# Logic_SchematicV4-w-DRC.net
KiCad netlist of a schematic drawn in EAGLE
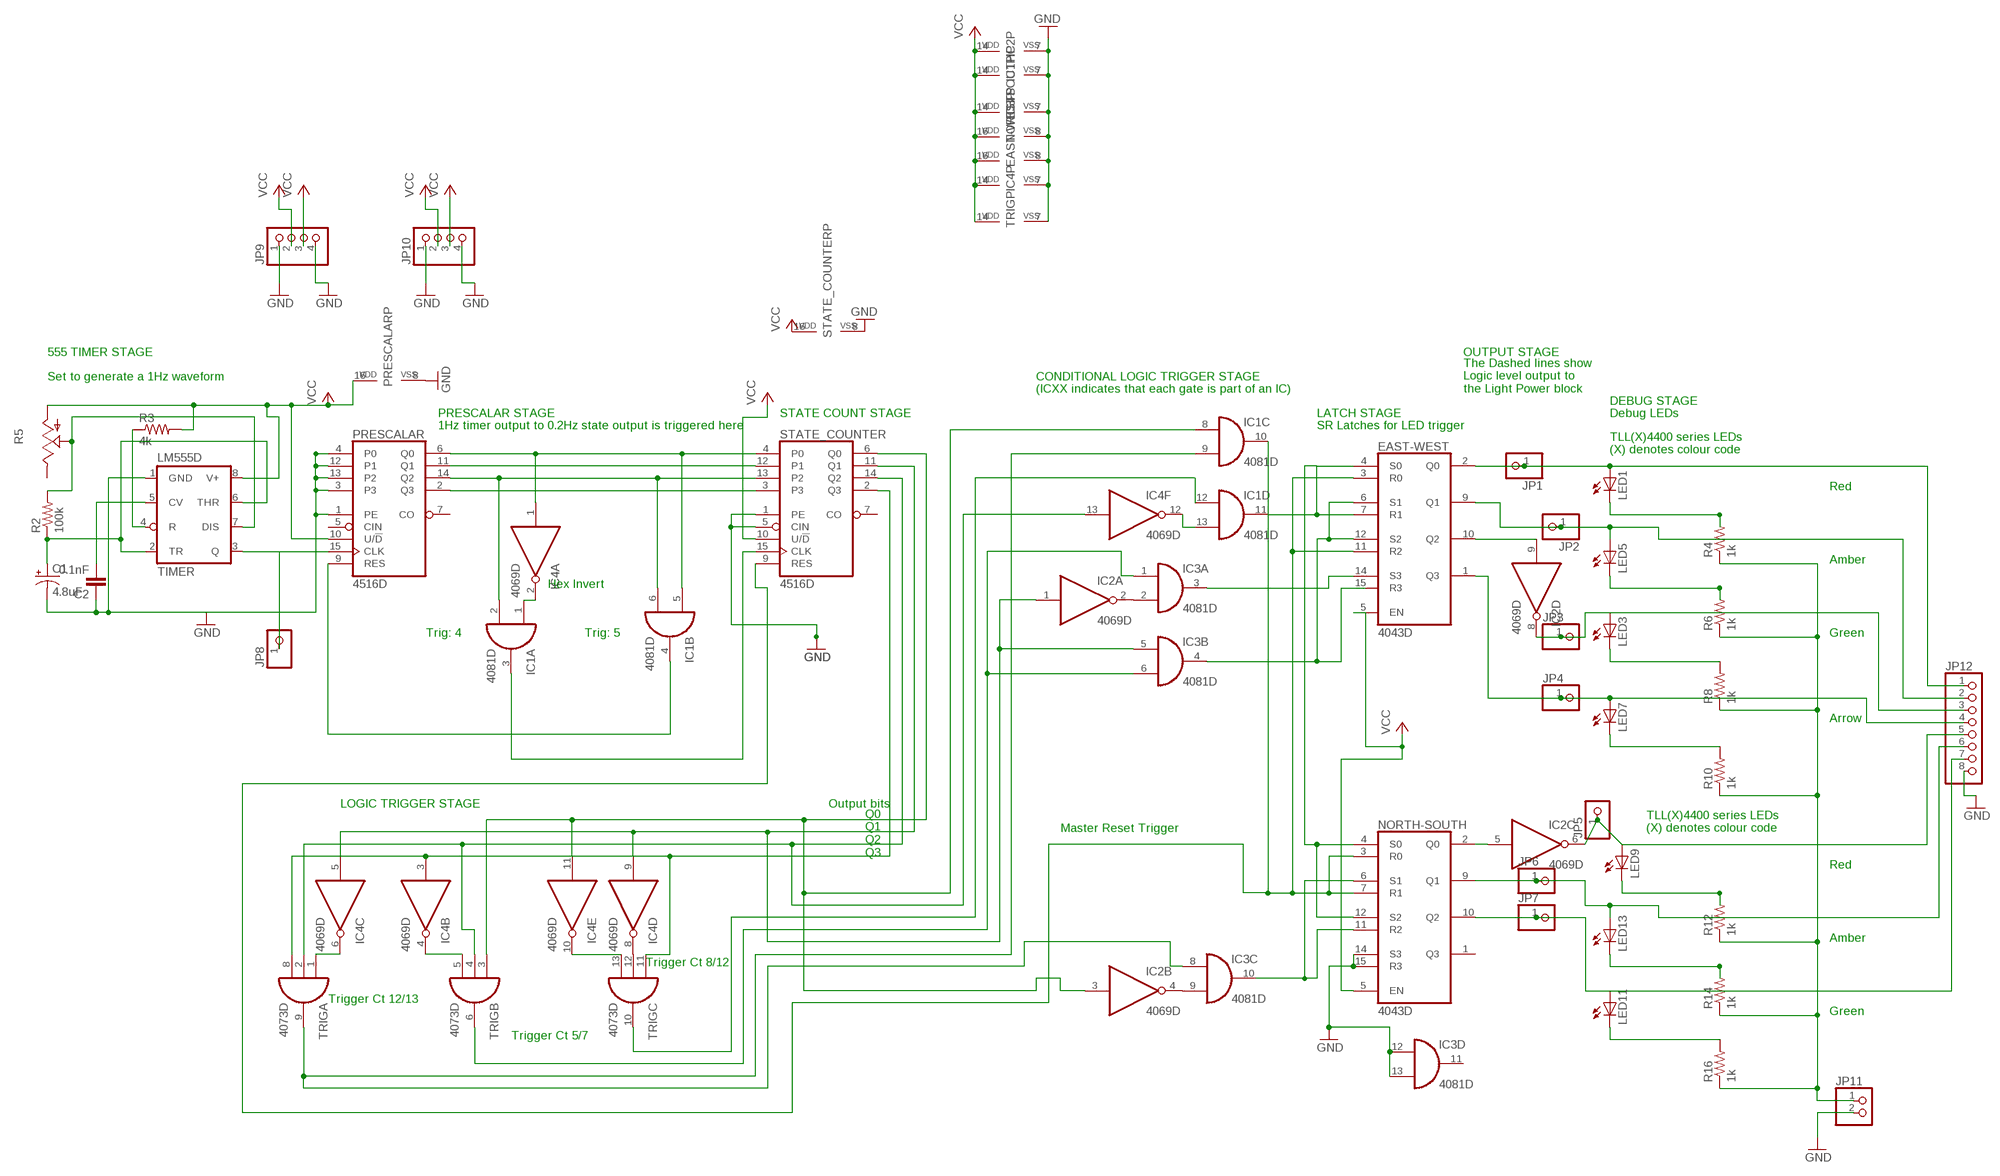
[diagram p0: schematic, sheet 1]

(export (version "E")
  (design (tool "Eeschema 10.0.6"))
  (components
    (comp (ref "C1")
      (value "4.8uF")
      (footprint "eagle-import:E5-8,5")
      (libsource (lib "eagle-import") (part "CPOL-USE5-8.5"))
    )
    (comp (ref "C2")
      (value "0.1nF")
      (footprint "eagle-import:C0805")
      (libsource (lib "eagle-import") (part "C-EUC0805"))
    )
    (comp (ref "EAST-WEST")
      (value "4043D")
      (footprint "eagle-import:SO16")
      (libsource (lib "eagle-import") (part "4043D"))
    )
    (comp (ref "IC1")
      (value "4081D")
      (footprint "eagle-import:SO14")
      (libsource (lib "eagle-import") (part "4081D"))
    )
    (comp (ref "IC2")
      (value "4069D")
      (footprint "eagle-import:SO14")
      (libsource (lib "eagle-import") (part "4069D"))
    )
    (comp (ref "IC3")
      (value "4081D")
      (footprint "eagle-import:SO14")
      (libsource (lib "eagle-import") (part "4081D"))
    )
    (comp (ref "IC4")
      (value "4069D")
      (footprint "eagle-import:SO14")
      (libsource (lib "eagle-import") (part "4069D"))
    )
    (comp (ref "JP1")
      (value "PINHD-1X1")
      (footprint "eagle-import:1X01")
      (libsource (lib "eagle-import") (part "PINHD-1X1"))
    )
    (comp (ref "JP2")
      (value "PINHD-1X1")
      (footprint "eagle-import:1X01")
      (libsource (lib "eagle-import") (part "PINHD-1X1"))
    )
    (comp (ref "JP3")
      (value "PINHD-1X1")
      (footprint "eagle-import:1X01")
      (libsource (lib "eagle-import") (part "PINHD-1X1"))
    )
    (comp (ref "JP4")
      (value "PINHD-1X1")
      (footprint "eagle-import:1X01")
      (libsource (lib "eagle-import") (part "PINHD-1X1"))
    )
    (comp (ref "JP5")
      (value "PINHD-1X1")
      (footprint "eagle-import:1X01")
      (libsource (lib "eagle-import") (part "PINHD-1X1"))
    )
    (comp (ref "JP6")
      (value "PINHD-1X1")
      (footprint "eagle-import:1X01")
      (libsource (lib "eagle-import") (part "PINHD-1X1"))
    )
    (comp (ref "JP7")
      (value "PINHD-1X1")
      (footprint "eagle-import:1X01")
      (libsource (lib "eagle-import") (part "PINHD-1X1"))
    )
    (comp (ref "JP8")
      (value "PINHD-1X1")
      (footprint "eagle-import:1X01")
      (libsource (lib "eagle-import") (part "PINHD-1X1"))
    )
    (comp (ref "JP9")
      (value "PINHD-1X4")
      (footprint "eagle-import:1X04")
      (libsource (lib "eagle-import") (part "PINHD-1X4"))
    )
    (comp (ref "JP10")
      (value "PINHD-1X4")
      (footprint "eagle-import:1X04")
      (libsource (lib "eagle-import") (part "PINHD-1X4"))
    )
    (comp (ref "JP11")
      (value "PINHD-1X2")
      (footprint "eagle-import:1X02")
      (libsource (lib "eagle-import") (part "PINHD-1X2"))
    )
    (comp (ref "JP12")
      (value "PINHD-1X8")
      (footprint "eagle-import:1X08")
      (libsource (lib "eagle-import") (part "PINHD-1X8"))
    )
    (comp (ref "LED1")
      (value "LEDCHIP-LED0805")
      (footprint "eagle-import:CHIP-LED0805")
      (libsource (lib "eagle-import") (part "LEDCHIP-LED0805"))
    )
    (comp (ref "LED3")
      (value "LEDCHIP-LED0805")
      (footprint "eagle-import:CHIP-LED0805")
      (libsource (lib "eagle-import") (part "LEDCHIP-LED0805"))
    )
    (comp (ref "LED5")
      (value "LEDCHIP-LED0805")
      (footprint "eagle-import:CHIP-LED0805")
      (libsource (lib "eagle-import") (part "LEDCHIP-LED0805"))
    )
    (comp (ref "LED7")
      (value "LEDCHIP-LED0805")
      (footprint "eagle-import:CHIP-LED0805")
      (libsource (lib "eagle-import") (part "LEDCHIP-LED0805"))
    )
    (comp (ref "LED9")
      (value "LEDCHIP-LED0805")
      (footprint "eagle-import:CHIP-LED0805")
      (libsource (lib "eagle-import") (part "LEDCHIP-LED0805"))
    )
    (comp (ref "LED11")
      (value "LEDCHIP-LED0805")
      (footprint "eagle-import:CHIP-LED0805")
      (libsource (lib "eagle-import") (part "LEDCHIP-LED0805"))
    )
    (comp (ref "LED13")
      (value "LEDCHIP-LED0805")
      (footprint "eagle-import:CHIP-LED0805")
      (libsource (lib "eagle-import") (part "LEDCHIP-LED0805"))
    )
    (comp (ref "NORTH-SOUTH")
      (value "4043D")
      (footprint "eagle-import:SO16")
      (libsource (lib "eagle-import") (part "4043D"))
    )
    (comp (ref "PRESCALAR")
      (value "4516D")
      (footprint "eagle-import:SO16")
      (libsource (lib "eagle-import") (part "4516D"))
    )
    (comp (ref "R2")
      (value "100k")
      (footprint "eagle-import:M0805")
      (libsource (lib "eagle-import") (part "R-US_M0805"))
    )
    (comp (ref "R3")
      (value "4k")
      (footprint "eagle-import:M0805")
      (libsource (lib "eagle-import") (part "R-US_M0805"))
    )
    (comp (ref "R4")
      (value "1k")
      (footprint "eagle-import:M0805")
      (libsource (lib "eagle-import") (part "R-US_M0805"))
    )
    (comp (ref "R5")
      (value "TRIM_US-B25P")
      (footprint "eagle-import:B25P")
      (libsource (lib "eagle-import") (part "TRIM_US-B25P"))
    )
    (comp (ref "R6")
      (value "1k")
      (footprint "eagle-import:M0805")
      (libsource (lib "eagle-import") (part "R-US_M0805"))
    )
    (comp (ref "R8")
      (value "1k")
      (footprint "eagle-import:M0805")
      (libsource (lib "eagle-import") (part "R-US_M0805"))
    )
    (comp (ref "R10")
      (value "1k")
      (footprint "eagle-import:M0805")
      (libsource (lib "eagle-import") (part "R-US_M0805"))
    )
    (comp (ref "R12")
      (value "1k")
      (footprint "eagle-import:M0805")
      (libsource (lib "eagle-import") (part "R-US_M0805"))
    )
    (comp (ref "R14")
      (value "1k")
      (footprint "eagle-import:M0805")
      (libsource (lib "eagle-import") (part "R-US_M0805"))
    )
    (comp (ref "R16")
      (value "1k")
      (footprint "eagle-import:M0805")
      (libsource (lib "eagle-import") (part "R-US_M0805"))
    )
    (comp (ref "STATE_COUNTER")
      (value "4516D")
      (footprint "eagle-import:SO16")
      (libsource (lib "eagle-import") (part "4516D"))
    )
    (comp (ref "TIMER")
      (value "LM555D")
      (footprint "eagle-import:SO08")
      (libsource (lib "eagle-import") (part "555DLM"))
    )
    (comp (ref "TRIG")
      (value "4073D")
      (footprint "eagle-import:SO14")
      (libsource (lib "eagle-import") (part "4073D"))
    )
  )
  (nets
    (net (code "1") (name "GND") (class "Default")
      (node (ref "C1") (pin "-") (pinfunction "-_-") (pintype "passive"))
      (node (ref "C2") (pin "1") (pinfunction "1_1") (pintype "passive"))
      (node (ref "EAST-WEST") (pin "8") (pinfunction "VSS_8") (pintype "power_in"))
      (node (ref "IC1") (pin "7") (pinfunction "VSS_7") (pintype "power_in"))
      (node (ref "IC2") (pin "7") (pinfunction "VSS_7") (pintype "power_in"))
      (node (ref "IC3") (pin "12") (pinfunction "I0_12") (pintype "input"))
      (node (ref "IC3") (pin "13") (pinfunction "I1_13") (pintype "input"))
      (node (ref "IC3") (pin "7") (pinfunction "VSS_7") (pintype "power_in"))
      (node (ref "IC4") (pin "7") (pinfunction "VSS_7") (pintype "power_in"))
      (node (ref "JP10") (pin "1") (pinfunction "1_1") (pintype "passive"))
      (node (ref "JP10") (pin "4") (pinfunction "4_4") (pintype "passive"))
      (node (ref "JP11") (pin "2") (pinfunction "2_2") (pintype "passive"))
      (node (ref "JP12") (pin "8") (pinfunction "8_8") (pintype "passive"))
      (node (ref "JP9") (pin "1") (pinfunction "1_1") (pintype "passive"))
      (node (ref "JP9") (pin "4") (pinfunction "4_4") (pintype "passive"))
      (node (ref "NORTH-SOUTH") (pin "14") (pinfunction "S3_14") (pintype "input"))
      (node (ref "NORTH-SOUTH") (pin "15") (pinfunction "R3_15") (pintype "input"))
      (node (ref "NORTH-SOUTH") (pin "8") (pinfunction "VSS_8") (pintype "power_in"))
      (node (ref "PRESCALAR") (pin "1") (pinfunction "PE_1") (pintype "input"))
      (node (ref "PRESCALAR") (pin "12") (pinfunction "P1_12") (pintype "input"))
      (node (ref "PRESCALAR") (pin "13") (pinfunction "P2_13") (pintype "input"))
      (node (ref "PRESCALAR") (pin "3") (pinfunction "P3_3") (pintype "input"))
      (node (ref "PRESCALAR") (pin "4") (pinfunction "P0_4") (pintype "input"))
      (node (ref "PRESCALAR") (pin "8") (pinfunction "VSS_8") (pintype "power_in"))
      (node (ref "STATE_COUNTER") (pin "1") (pinfunction "PE_1") (pintype "input"))
      (node (ref "STATE_COUNTER") (pin "5") (pinfunction "CIN_5") (pintype "input"))
      (node (ref "STATE_COUNTER") (pin "8") (pinfunction "VSS_8") (pintype "power_in"))
      (node (ref "TIMER") (pin "1") (pinfunction "GND_1") (pintype "power_in"))
      (node (ref "TRIG") (pin "7") (pinfunction "VSS_7") (pintype "power_in"))
    )
    (net (code "2") (name "Net-(EAST-WESTA-Q0)") (class "Default")
      (node (ref "EAST-WEST") (pin "2") (pinfunction "Q0_2") (pintype "output"))
      (node (ref "JP1") (pin "1") (pinfunction "1_1") (pintype "passive"))
      (node (ref "JP12") (pin "1") (pinfunction "1_1") (pintype "passive"))
      (node (ref "LED1") (pin "A") (pinfunction "A_A") (pintype "passive"))
    )
    (net (code "3") (name "Net-(EAST-WESTA-Q1)") (class "Default")
      (node (ref "EAST-WEST") (pin "9") (pinfunction "Q1_9") (pintype "output"))
      (node (ref "JP12") (pin "2") (pinfunction "2_2") (pintype "passive"))
      (node (ref "JP2") (pin "1") (pinfunction "1_1") (pintype "passive"))
      (node (ref "LED5") (pin "A") (pinfunction "A_A") (pintype "passive"))
    )
    (net (code "4") (name "Net-(EAST-WESTA-Q2)") (class "Default")
      (node (ref "EAST-WEST") (pin "10") (pinfunction "Q2_10") (pintype "output"))
      (node (ref "IC2") (pin "9") (pinfunction "I_9") (pintype "input"))
    )
    (net (code "5") (name "Net-(EAST-WESTA-Q3)") (class "Default")
      (node (ref "EAST-WEST") (pin "1") (pinfunction "Q3_1") (pintype "output"))
      (node (ref "JP12") (pin "4") (pinfunction "4_4") (pintype "passive"))
      (node (ref "JP4") (pin "1") (pinfunction "1_1") (pintype "passive"))
      (node (ref "LED7") (pin "A") (pinfunction "A_A") (pintype "passive"))
    )
    (net (code "6") (name "Net-(EAST-WESTA-R0)") (class "Default")
      (node (ref "EAST-WEST") (pin "11") (pinfunction "R2_11") (pintype "input"))
      (node (ref "EAST-WEST") (pin "3") (pinfunction "R0_3") (pintype "input"))
      (node (ref "IC1") (pin "10") (pinfunction "O_10") (pintype "output"))
      (node (ref "NORTH-SOUTH") (pin "3") (pinfunction "R0_3") (pintype "input"))
      (node (ref "NORTH-SOUTH") (pin "7") (pinfunction "R1_7") (pintype "input"))
      (node (ref "STATE_COUNTER") (pin "9") (pinfunction "RES_9") (pintype "input"))
    )
    (net (code "7") (name "Net-(EAST-WESTA-R1)") (class "Default")
      (node (ref "EAST-WEST") (pin "4") (pinfunction "S0_4") (pintype "input"))
      (node (ref "EAST-WEST") (pin "7") (pinfunction "R1_7") (pintype "input"))
      (node (ref "IC1") (pin "11") (pinfunction "O_11") (pintype "output"))
      (node (ref "NORTH-SOUTH") (pin "12") (pinfunction "S2_12") (pintype "input"))
      (node (ref "NORTH-SOUTH") (pin "4") (pinfunction "S0_4") (pintype "input"))
    )
    (net (code "8") (name "Net-(EAST-WESTA-S1)") (class "Default")
      (node (ref "EAST-WEST") (pin "12") (pinfunction "S2_12") (pintype "input"))
      (node (ref "EAST-WEST") (pin "6") (pinfunction "S1_6") (pintype "input"))
      (node (ref "IC3") (pin "4") (pinfunction "O_4") (pintype "output"))
    )
    (net (code "9") (name "Net-(EAST-WESTA-S3)") (class "Default")
      (node (ref "EAST-WEST") (pin "14") (pinfunction "S3_14") (pintype "input"))
      (node (ref "IC3") (pin "3") (pinfunction "O_3") (pintype "output"))
    )
    (net (code "10") (name "Net-(IC1A-I0)") (class "Default")
      (node (ref "IC1") (pin "1") (pinfunction "I0_1") (pintype "input"))
      (node (ref "IC4") (pin "2") (pinfunction "O_2") (pintype "output"))
    )
    (net (code "11") (name "Net-(IC1A-I1)") (class "Default")
      (node (ref "IC1") (pin "2") (pinfunction "I1_2") (pintype "input"))
      (node (ref "IC1") (pin "6") (pinfunction "I1_6") (pintype "input"))
      (node (ref "PRESCALAR") (pin "14") (pinfunction "Q2_14") (pintype "output"))
      (node (ref "STATE_COUNTER") (pin "13") (pinfunction "P2_13") (pintype "input"))
    )
    (net (code "12") (name "Net-(IC1A-O)") (class "Default")
      (node (ref "IC1") (pin "3") (pinfunction "O_3") (pintype "output"))
      (node (ref "STATE_COUNTER") (pin "15") (pinfunction "CLK_15") (pintype "input"))
    )
    (net (code "13") (name "Net-(IC1B-I0)") (class "Default")
      (node (ref "IC1") (pin "5") (pinfunction "I0_5") (pintype "input"))
      (node (ref "IC4") (pin "1") (pinfunction "I_1") (pintype "input"))
      (node (ref "PRESCALAR") (pin "6") (pinfunction "Q0_6") (pintype "output"))
      (node (ref "STATE_COUNTER") (pin "4") (pinfunction "P0_4") (pintype "input"))
    )
    (net (code "14") (name "Net-(IC1B-O)") (class "Default")
      (node (ref "IC1") (pin "4") (pinfunction "O_4") (pintype "output"))
      (node (ref "PRESCALAR") (pin "9") (pinfunction "RES_9") (pintype "input"))
    )
    (net (code "15") (name "Net-(IC1C-I0)") (class "Default")
      (node (ref "IC1") (pin "8") (pinfunction "I0_8") (pintype "input"))
      (node (ref "IC2") (pin "3") (pinfunction "I_3") (pintype "input"))
      (node (ref "IC4") (pin "11") (pinfunction "I_11") (pintype "input"))
      (node (ref "STATE_COUNTER") (pin "6") (pinfunction "Q0_6") (pintype "output"))
      (node (ref "TRIG") (pin "3") (pinfunction "I0_3") (pintype "input"))
    )
    (net (code "16") (name "Net-(IC1C-I1)") (class "Default")
      (node (ref "IC1") (pin "9") (pinfunction "I1_9") (pintype "input"))
      (node (ref "IC3") (pin "8") (pinfunction "I0_8") (pintype "input"))
      (node (ref "TRIG") (pin "9") (pinfunction "O_9") (pintype "output"))
    )
    (net (code "17") (name "Net-(IC1D-I0)") (class "Default")
      (node (ref "IC1") (pin "12") (pinfunction "I0_12") (pintype "input"))
      (node (ref "TRIG") (pin "10") (pinfunction "O_10") (pintype "output"))
    )
    (net (code "18") (name "Net-(IC1D-I1)") (class "Default")
      (node (ref "IC1") (pin "13") (pinfunction "I1_13") (pintype "input"))
      (node (ref "IC4") (pin "12") (pinfunction "O_12") (pintype "output"))
    )
    (net (code "19") (name "Net-(IC2A-I)") (class "Default")
      (node (ref "IC2") (pin "1") (pinfunction "I_1") (pintype "input"))
      (node (ref "IC3") (pin "5") (pinfunction "I0_5") (pintype "input"))
      (node (ref "IC4") (pin "5") (pinfunction "I_5") (pintype "input"))
      (node (ref "IC4") (pin "9") (pinfunction "I_9") (pintype "input"))
      (node (ref "STATE_COUNTER") (pin "11") (pinfunction "Q1_11") (pintype "output"))
    )
    (net (code "20") (name "Net-(IC2A-O)") (class "Default")
      (node (ref "IC2") (pin "2") (pinfunction "O_2") (pintype "output"))
      (node (ref "IC3") (pin "2") (pinfunction "I1_2") (pintype "input"))
    )
    (net (code "21") (name "Net-(IC2B-O)") (class "Default")
      (node (ref "IC2") (pin "4") (pinfunction "O_4") (pintype "output"))
      (node (ref "IC3") (pin "9") (pinfunction "I1_9") (pintype "input"))
    )
    (net (code "22") (name "Net-(IC2C-I)") (class "Default")
      (node (ref "IC2") (pin "5") (pinfunction "I_5") (pintype "input"))
      (node (ref "NORTH-SOUTH") (pin "2") (pinfunction "Q0_2") (pintype "output"))
    )
    (net (code "23") (name "Net-(IC2C-O)") (class "Default")
      (node (ref "IC2") (pin "6") (pinfunction "O_6") (pintype "output"))
      (node (ref "JP12") (pin "5") (pinfunction "5_5") (pintype "passive"))
      (node (ref "JP5") (pin "1") (pinfunction "1_1") (pintype "passive"))
      (node (ref "LED9") (pin "A") (pinfunction "A_A") (pintype "passive"))
    )
    (net (code "24") (name "Net-(IC2D-O)") (class "Default")
      (node (ref "IC2") (pin "8") (pinfunction "O_8") (pintype "output"))
      (node (ref "JP12") (pin "3") (pinfunction "3_3") (pintype "passive"))
      (node (ref "JP3") (pin "1") (pinfunction "1_1") (pintype "passive"))
      (node (ref "LED3") (pin "A") (pinfunction "A_A") (pintype "passive"))
    )
    (net (code "25") (name "Net-(IC3A-I0)") (class "Default")
      (node (ref "IC3") (pin "1") (pinfunction "I0_1") (pintype "input"))
      (node (ref "IC3") (pin "6") (pinfunction "I1_6") (pintype "input"))
      (node (ref "TRIG") (pin "6") (pinfunction "O_6") (pintype "output"))
    )
    (net (code "26") (name "Net-(IC3C-O)") (class "Default")
      (node (ref "IC3") (pin "10") (pinfunction "O_10") (pintype "output"))
      (node (ref "NORTH-SOUTH") (pin "11") (pinfunction "R2_11") (pintype "input"))
      (node (ref "NORTH-SOUTH") (pin "6") (pinfunction "S1_6") (pintype "input"))
    )
    (net (code "27") (name "Net-(IC4B-I)") (class "Default")
      (node (ref "IC4") (pin "3") (pinfunction "I_3") (pintype "input"))
      (node (ref "STATE_COUNTER") (pin "2") (pinfunction "Q3_2") (pintype "output"))
      (node (ref "TRIG") (pin "11") (pinfunction "I0_11") (pintype "input"))
      (node (ref "TRIG") (pin "8") (pinfunction "I2_8") (pintype "input"))
    )
    (net (code "28") (name "Net-(IC4B-O)") (class "Default")
      (node (ref "IC4") (pin "4") (pinfunction "O_4") (pintype "output"))
      (node (ref "TRIG") (pin "5") (pinfunction "I2_5") (pintype "input"))
    )
    (net (code "29") (name "Net-(IC4C-O)") (class "Default")
      (node (ref "IC4") (pin "6") (pinfunction "O_6") (pintype "output"))
      (node (ref "TRIG") (pin "1") (pinfunction "I0_1") (pintype "input"))
    )
    (net (code "30") (name "Net-(IC4D-O)") (class "Default")
      (node (ref "IC4") (pin "8") (pinfunction "O_8") (pintype "output"))
      (node (ref "TRIG") (pin "12") (pinfunction "I1_12") (pintype "input"))
    )
    (net (code "31") (name "Net-(IC4E-O)") (class "Default")
      (node (ref "IC4") (pin "10") (pinfunction "O_10") (pintype "output"))
      (node (ref "TRIG") (pin "13") (pinfunction "I2_13") (pintype "input"))
    )
    (net (code "32") (name "Net-(IC4F-I)") (class "Default")
      (node (ref "IC4") (pin "13") (pinfunction "I_13") (pintype "input"))
      (node (ref "STATE_COUNTER") (pin "14") (pinfunction "Q2_14") (pintype "output"))
      (node (ref "TRIG") (pin "2") (pinfunction "I1_2") (pintype "input"))
      (node (ref "TRIG") (pin "4") (pinfunction "I1_4") (pintype "input"))
    )
    (net (code "33") (name "Net-(JP11-Pad1)") (class "Default")
      (node (ref "JP11") (pin "1") (pinfunction "1_1") (pintype "passive"))
      (node (ref "R10") (pin "1") (pinfunction "1_1") (pintype "passive"))
      (node (ref "R12") (pin "1") (pinfunction "1_1") (pintype "passive"))
      (node (ref "R14") (pin "1") (pinfunction "1_1") (pintype "passive"))
      (node (ref "R16") (pin "1") (pinfunction "1_1") (pintype "passive"))
      (node (ref "R4") (pin "1") (pinfunction "1_1") (pintype "passive"))
      (node (ref "R6") (pin "1") (pinfunction "1_1") (pintype "passive"))
      (node (ref "R8") (pin "1") (pinfunction "1_1") (pintype "passive"))
    )
    (net (code "34") (name "Net-(LED1-PadC)") (class "Default")
      (node (ref "LED1") (pin "C") (pinfunction "C_C") (pintype "passive"))
      (node (ref "R4") (pin "2") (pinfunction "2_2") (pintype "passive"))
    )
    (net (code "35") (name "Net-(LED3-PadC)") (class "Default")
      (node (ref "LED3") (pin "C") (pinfunction "C_C") (pintype "passive"))
      (node (ref "R8") (pin "2") (pinfunction "2_2") (pintype "passive"))
    )
    (net (code "36") (name "Net-(LED5-PadC)") (class "Default")
      (node (ref "LED5") (pin "C") (pinfunction "C_C") (pintype "passive"))
      (node (ref "R6") (pin "2") (pinfunction "2_2") (pintype "passive"))
    )
    (net (code "37") (name "Net-(LED7-PadC)") (class "Default")
      (node (ref "LED7") (pin "C") (pinfunction "C_C") (pintype "passive"))
      (node (ref "R10") (pin "2") (pinfunction "2_2") (pintype "passive"))
    )
    (net (code "38") (name "Net-(LED9-PadC)") (class "Default")
      (node (ref "LED9") (pin "C") (pinfunction "C_C") (pintype "passive"))
      (node (ref "R12") (pin "2") (pinfunction "2_2") (pintype "passive"))
    )
    (net (code "39") (name "Net-(LED11-PadC)") (class "Default")
      (node (ref "LED11") (pin "C") (pinfunction "C_C") (pintype "passive"))
      (node (ref "R16") (pin "2") (pinfunction "2_2") (pintype "passive"))
    )
    (net (code "40") (name "Net-(LED13-PadC)") (class "Default")
      (node (ref "LED13") (pin "C") (pinfunction "C_C") (pintype "passive"))
      (node (ref "R14") (pin "2") (pinfunction "2_2") (pintype "passive"))
    )
    (net (code "41") (name "Net-(NORTH-SOUTHA-Q1)") (class "Default")
      (node (ref "JP12") (pin "6") (pinfunction "6_6") (pintype "passive"))
      (node (ref "JP6") (pin "1") (pinfunction "1_1") (pintype "passive"))
      (node (ref "LED13") (pin "A") (pinfunction "A_A") (pintype "passive"))
      (node (ref "NORTH-SOUTH") (pin "9") (pinfunction "Q1_9") (pintype "output"))
    )
    (net (code "42") (name "Net-(NORTH-SOUTHA-Q2)") (class "Default")
      (node (ref "JP12") (pin "7") (pinfunction "7_7") (pintype "passive"))
      (node (ref "JP7") (pin "1") (pinfunction "1_1") (pintype "passive"))
      (node (ref "LED11") (pin "A") (pinfunction "A_A") (pintype "passive"))
      (node (ref "NORTH-SOUTH") (pin "10") (pinfunction "Q2_10") (pintype "output"))
    )
    (net (code "43") (name "Net-(PRESCALARA-CLK)") (class "Default")
      (node (ref "JP8") (pin "1") (pinfunction "1_1") (pintype "passive"))
      (node (ref "PRESCALAR") (pin "15") (pinfunction "CLK_15") (pintype "input"))
      (node (ref "TIMER") (pin "3") (pinfunction "Q_3") (pintype "output"))
    )
    (net (code "44") (name "Net-(PRESCALARA-Q1)") (class "Default")
      (node (ref "PRESCALAR") (pin "11") (pinfunction "Q1_11") (pintype "output"))
      (node (ref "STATE_COUNTER") (pin "12") (pinfunction "P1_12") (pintype "input"))
    )
    (net (code "45") (name "Net-(PRESCALARA-Q3)") (class "Default")
      (node (ref "PRESCALAR") (pin "2") (pinfunction "Q3_2") (pintype "output"))
      (node (ref "STATE_COUNTER") (pin "3") (pinfunction "P3_3") (pintype "input"))
    )
    (net (code "46") (name "Net-(TIMER-CV)") (class "Default")
      (node (ref "C2") (pin "2") (pinfunction "2_2") (pintype "passive"))
      (node (ref "TIMER") (pin "5") (pinfunction "CV_5") (pintype "input"))
    )
    (net (code "47") (name "Net-(TIMER-DIS)") (class "Default")
      (node (ref "R2") (pin "2") (pinfunction "2_2") (pintype "passive"))
      (node (ref "R5") (pin "S") (pinfunction "S_S") (pintype "passive"))
      (node (ref "TIMER") (pin "7") (pinfunction "DIS_7") (pintype "input"))
    )
    (net (code "48") (name "Net-(TIMER-R)") (class "Default")
      (node (ref "R3") (pin "1") (pinfunction "1_1") (pintype "passive"))
      (node (ref "TIMER") (pin "4") (pinfunction "R_4") (pintype "input"))
    )
    (net (code "49") (name "Net-(TIMER-THR)") (class "Default")
      (node (ref "C1") (pin "+") (pinfunction "+_+") (pintype "passive"))
      (node (ref "R2") (pin "1") (pinfunction "1_1") (pintype "passive"))
      (node (ref "TIMER") (pin "2") (pinfunction "TR_2") (pintype "input"))
      (node (ref "TIMER") (pin "6") (pinfunction "THR_6") (pintype "input"))
    )
    (net (code "50") (name "VCC") (class "Default")
      (node (ref "EAST-WEST") (pin "16") (pinfunction "VDD_16") (pintype "power_in"))
      (node (ref "EAST-WEST") (pin "5") (pinfunction "EN_5") (pintype "input"))
      (node (ref "IC1") (pin "14") (pinfunction "VDD_14") (pintype "power_in"))
      (node (ref "IC2") (pin "14") (pinfunction "VDD_14") (pintype "power_in"))
      (node (ref "IC3") (pin "14") (pinfunction "VDD_14") (pintype "power_in"))
      (node (ref "IC4") (pin "14") (pinfunction "VDD_14") (pintype "power_in"))
      (node (ref "JP10") (pin "2") (pinfunction "2_2") (pintype "passive"))
      (node (ref "JP10") (pin "3") (pinfunction "3_3") (pintype "passive"))
      (node (ref "JP9") (pin "2") (pinfunction "2_2") (pintype "passive"))
      (node (ref "JP9") (pin "3") (pinfunction "3_3") (pintype "passive"))
      (node (ref "NORTH-SOUTH") (pin "16") (pinfunction "VDD_16") (pintype "power_in"))
      (node (ref "NORTH-SOUTH") (pin "5") (pinfunction "EN_5") (pintype "input"))
      (node (ref "PRESCALAR") (pin "10") (pinfunction "U/~{D}_10") (pintype "input"))
      (node (ref "PRESCALAR") (pin "16") (pinfunction "VDD_16") (pintype "power_in"))
      (node (ref "R3") (pin "2") (pinfunction "2_2") (pintype "passive"))
      (node (ref "R5") (pin "A") (pinfunction "A_A") (pintype "passive"))
      (node (ref "STATE_COUNTER") (pin "10") (pinfunction "U/~{D}_10") (pintype "input"))
      (node (ref "STATE_COUNTER") (pin "16") (pinfunction "VDD_16") (pintype "power_in"))
      (node (ref "TIMER") (pin "8") (pinfunction "V+_8") (pintype "power_in"))
      (node (ref "TRIG") (pin "14") (pinfunction "VDD_14") (pintype "power_in"))
    )
    (net (code "51") (name "unconnected-(EAST-WESTA-R3-Pad15)") (class "Default")
      (node (ref "EAST-WEST") (pin "15") (pinfunction "R3_15") (pintype "input"))
    )
    (net (code "52") (name "unconnected-(IC3D-O-Pad11)") (class "Default")
      (node (ref "IC3") (pin "11") (pinfunction "O_11") (pintype "output"))
    )
    (net (code "53") (name "unconnected-(NORTH-SOUTHA-Q3-Pad1)") (class "Default")
      (node (ref "NORTH-SOUTH") (pin "1") (pinfunction "Q3_1") (pintype "output"))
    )
    (net (code "54") (name "unconnected-(PRESCALARA-CIN-Pad5)") (class "Default")
      (node (ref "PRESCALAR") (pin "5") (pinfunction "CIN_5") (pintype "input"))
    )
    (net (code "55") (name "unconnected-(PRESCALARA-CO-Pad7)") (class "Default")
      (node (ref "PRESCALAR") (pin "7") (pinfunction "CO_7") (pintype "output"))
    )
    (net (code "56") (name "unconnected-(R5-PadE)") (class "Default")
      (node (ref "R5") (pin "E") (pinfunction "E_E") (pintype "passive"))
    )
    (net (code "57") (name "unconnected-(STATE_COUNTERA-CO-Pad7)") (class "Default")
      (node (ref "STATE_COUNTER") (pin "7") (pinfunction "CO_7") (pintype "output"))
    )
  )
)
